# M869D.net
KiCad netlist of a schematic drawn in EAGLE
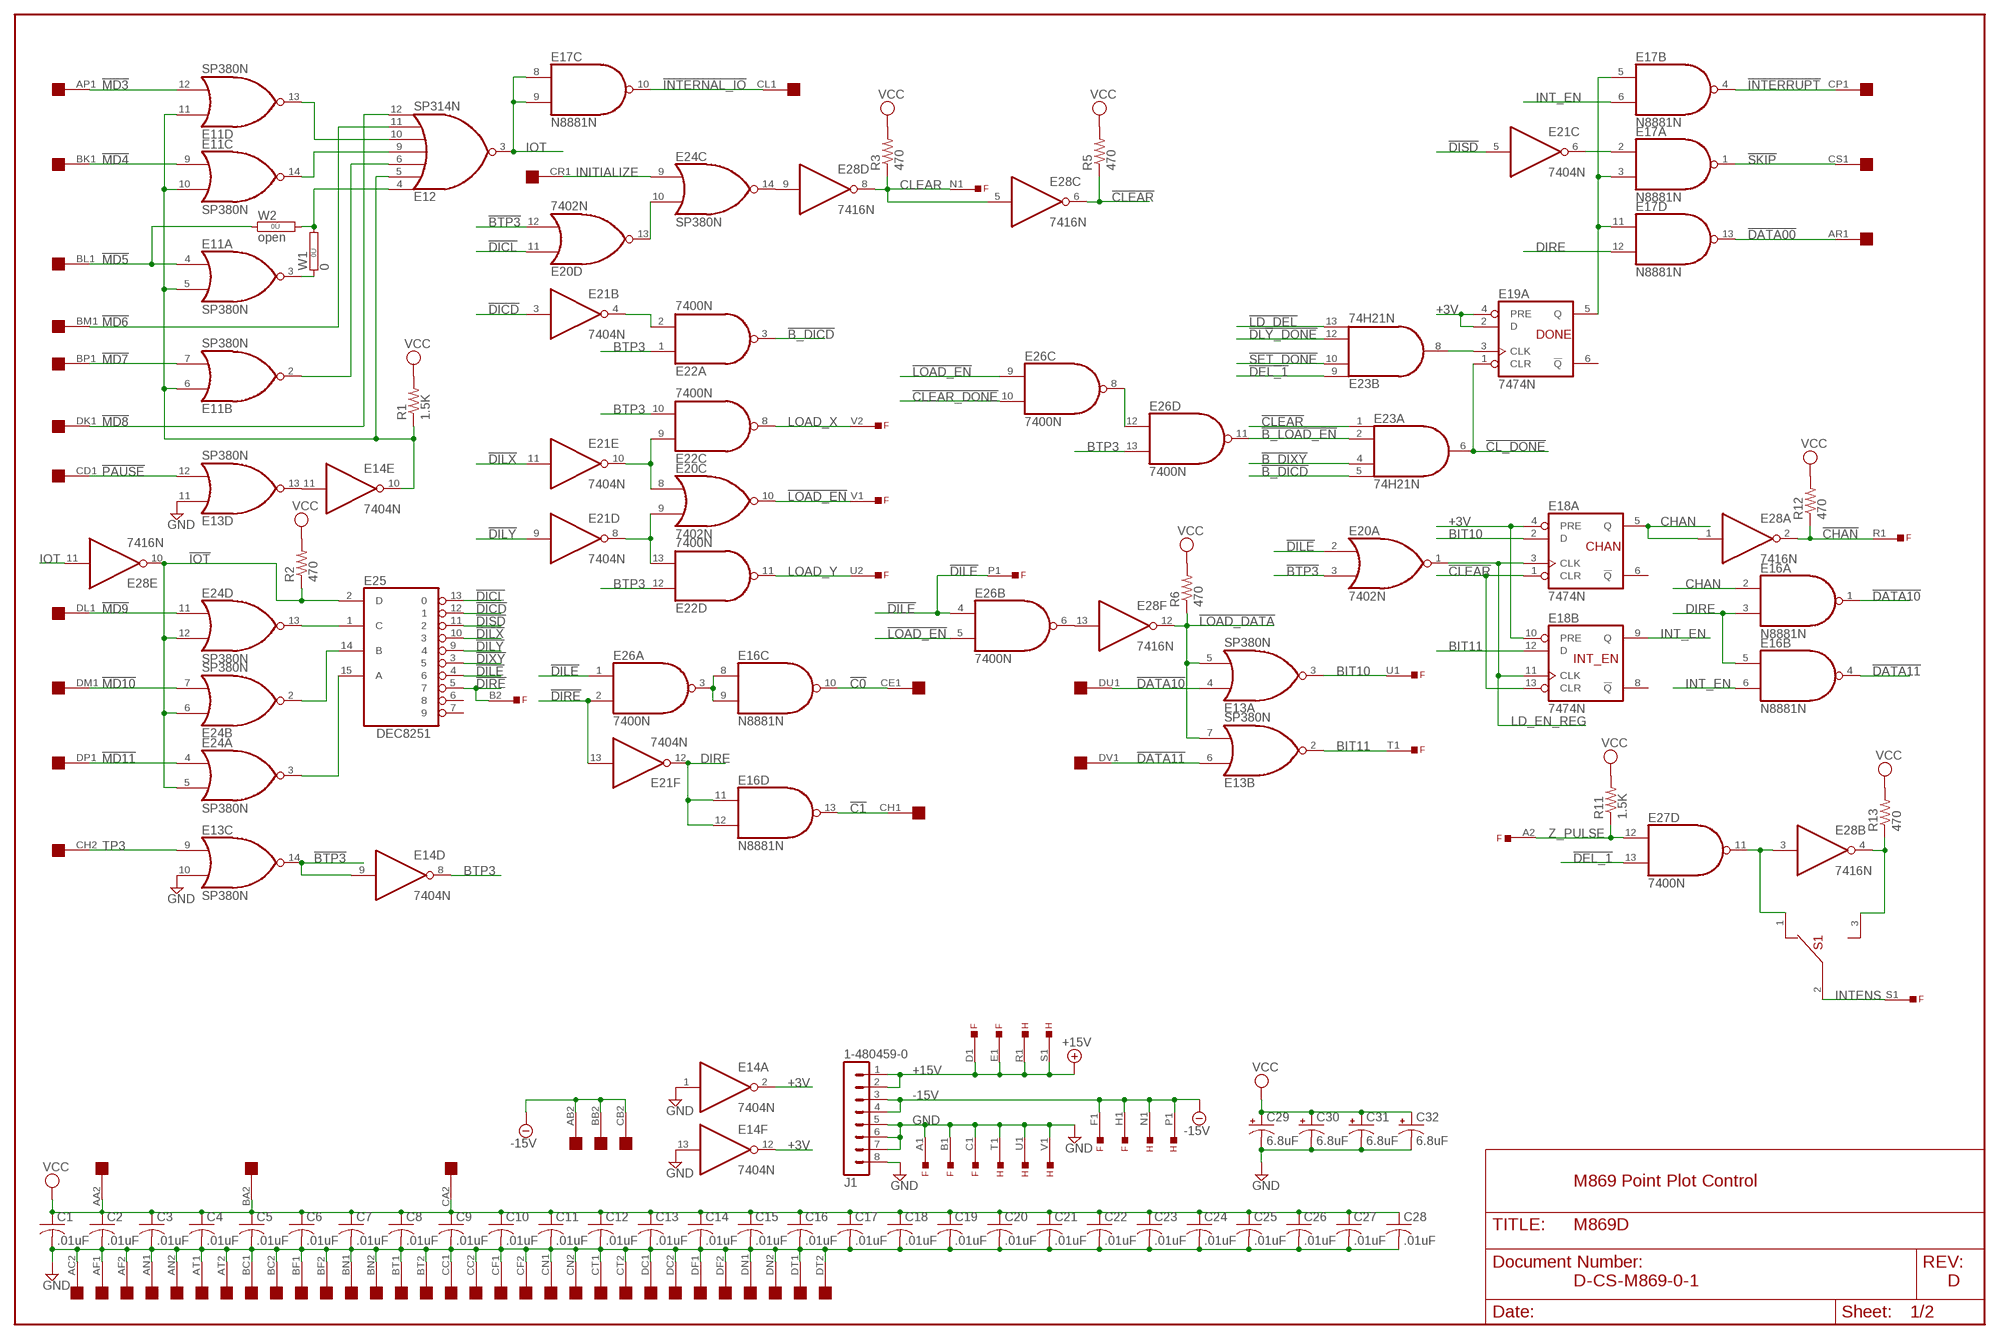
[diagram p0: schematic, sheet 1]
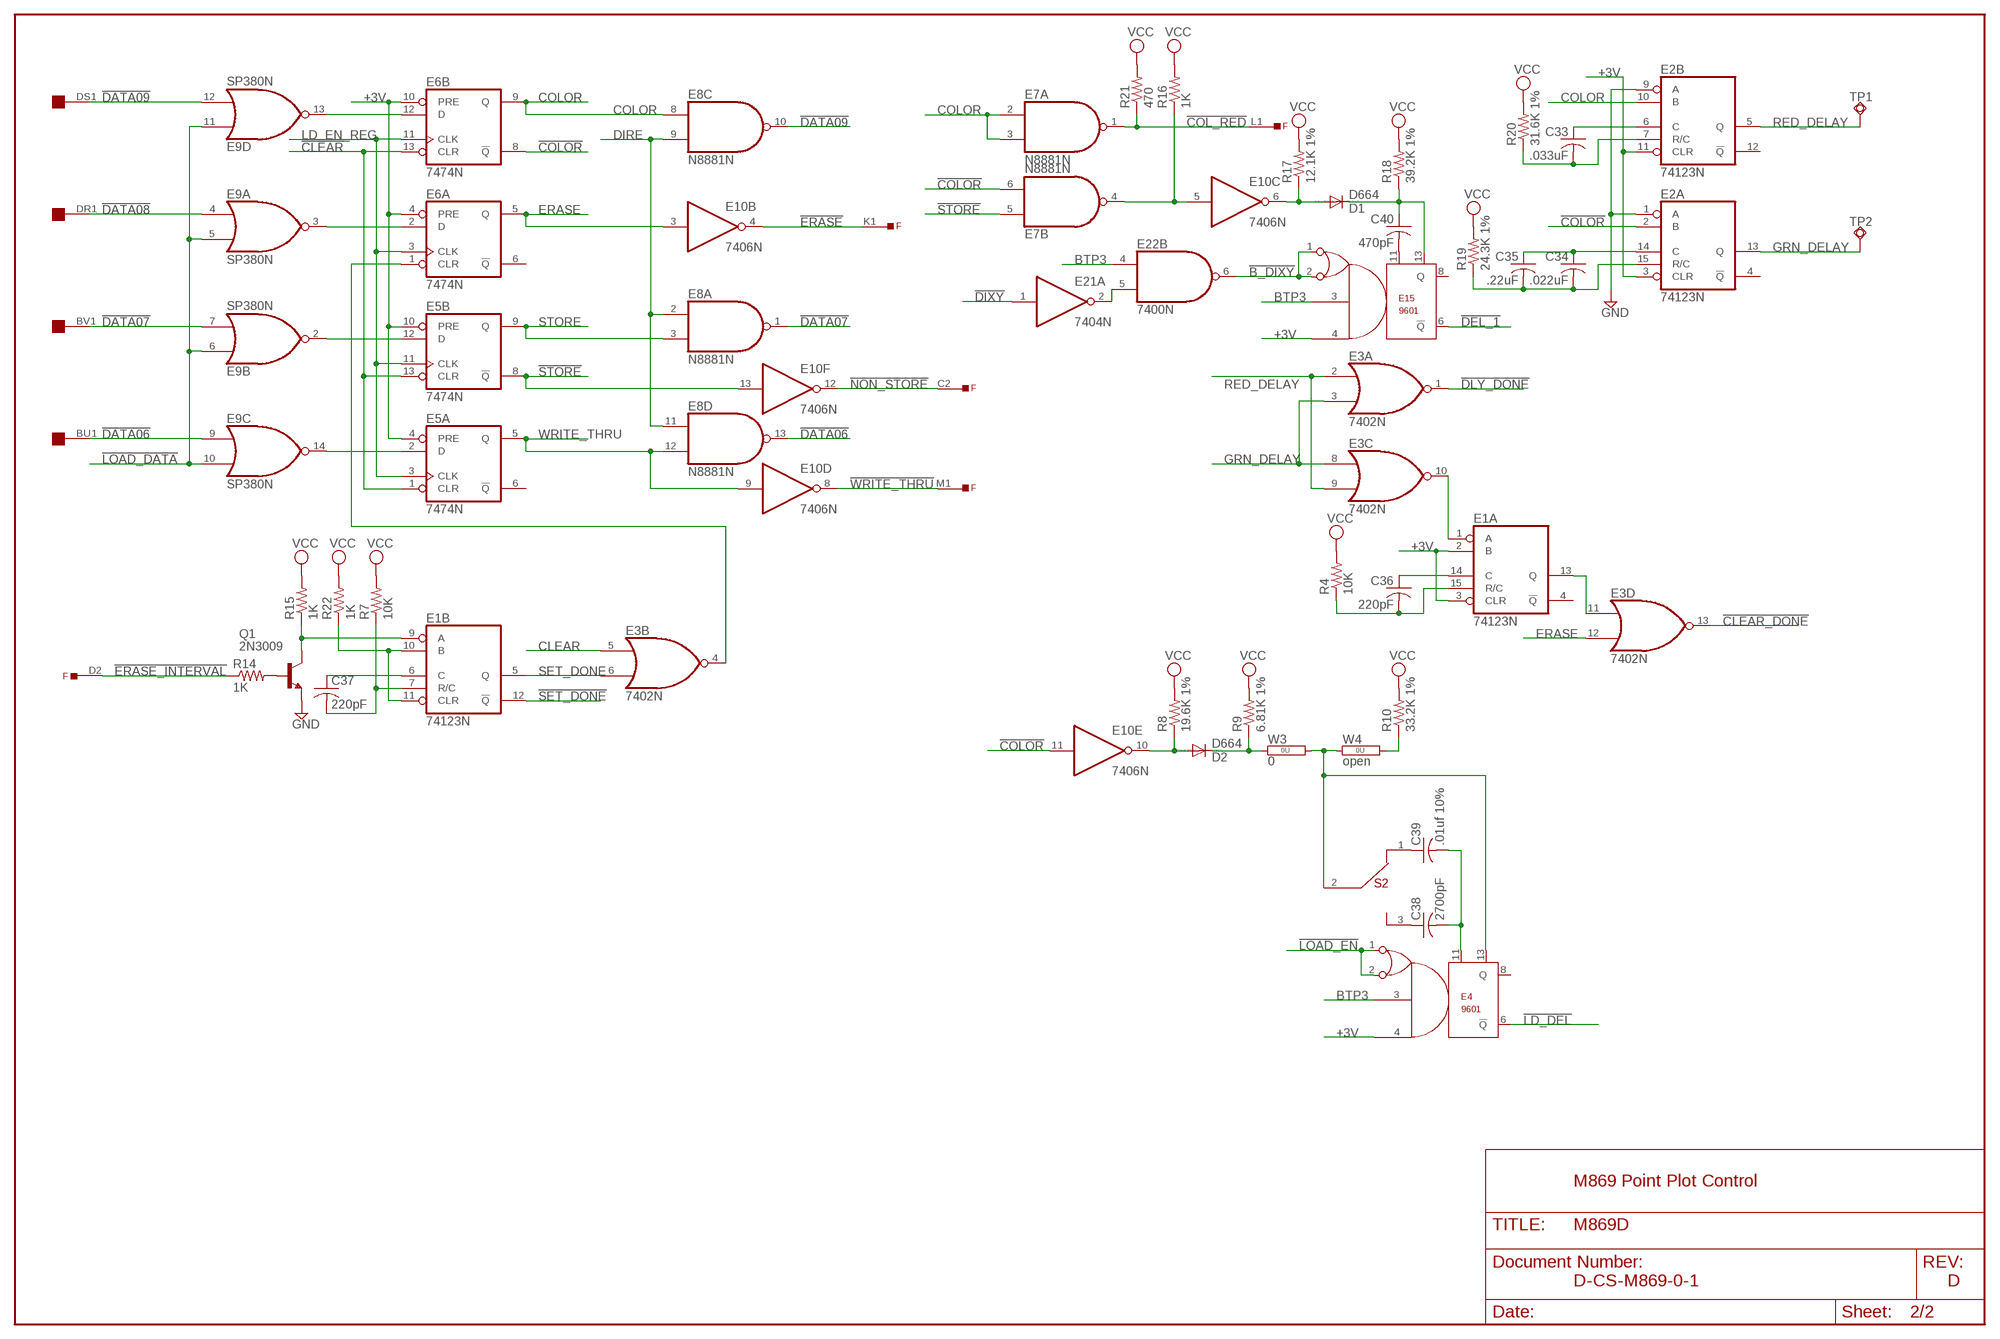
[diagram p1: schematic, sheet 2]

(export (version "E")
  (design (tool "Eeschema 10.0.6"))
  (components
    (comp (ref "C1")
      (value ".01uF")
      (footprint "eagle-import:C063-025X075")
      (libsource (lib "eagle-import") (part "C-US"))
    )
    (comp (ref "C2")
      (value ".01uF")
      (footprint "eagle-import:C063-025X075")
      (libsource (lib "eagle-import") (part "C-US"))
    )
    (comp (ref "C3")
      (value ".01uF")
      (footprint "eagle-import:C063-025X075")
      (libsource (lib "eagle-import") (part "C-US"))
    )
    (comp (ref "C4")
      (value ".01uF")
      (footprint "eagle-import:C063-025X075")
      (libsource (lib "eagle-import") (part "C-US"))
    )
    (comp (ref "C5")
      (value ".01uF")
      (footprint "eagle-import:C063-025X075")
      (libsource (lib "eagle-import") (part "C-US"))
    )
    (comp (ref "C6")
      (value ".01uF")
      (footprint "eagle-import:C063-025X075")
      (libsource (lib "eagle-import") (part "C-US"))
    )
    (comp (ref "C7")
      (value ".01uF")
      (footprint "eagle-import:C063-025X075")
      (libsource (lib "eagle-import") (part "C-US"))
    )
    (comp (ref "C8")
      (value ".01uF")
      (footprint "eagle-import:C063-025X075")
      (libsource (lib "eagle-import") (part "C-US"))
    )
    (comp (ref "C9")
      (value ".01uF")
      (footprint "eagle-import:C063-025X075")
      (libsource (lib "eagle-import") (part "C-US"))
    )
    (comp (ref "C10")
      (value ".01uF")
      (footprint "eagle-import:C063-025X075")
      (libsource (lib "eagle-import") (part "C-US"))
    )
    (comp (ref "C11")
      (value ".01uF")
      (footprint "eagle-import:C063-025X075")
      (libsource (lib "eagle-import") (part "C-US"))
    )
    (comp (ref "C12")
      (value ".01uF")
      (footprint "eagle-import:C063-025X075")
      (libsource (lib "eagle-import") (part "C-US"))
    )
    (comp (ref "C13")
      (value ".01uF")
      (footprint "eagle-import:C063-025X075")
      (libsource (lib "eagle-import") (part "C-US"))
    )
    (comp (ref "C14")
      (value ".01uF")
      (footprint "eagle-import:C063-025X075")
      (libsource (lib "eagle-import") (part "C-US"))
    )
    (comp (ref "C15")
      (value ".01uF")
      (footprint "eagle-import:C063-025X075")
      (libsource (lib "eagle-import") (part "C-US"))
    )
    (comp (ref "C16")
      (value ".01uF")
      (footprint "eagle-import:C063-025X075")
      (libsource (lib "eagle-import") (part "C-US"))
    )
    (comp (ref "C17")
      (value ".01uF")
      (footprint "eagle-import:C063-025X075")
      (libsource (lib "eagle-import") (part "C-US"))
    )
    (comp (ref "C18")
      (value ".01uF")
      (footprint "eagle-import:C063-025X075")
      (libsource (lib "eagle-import") (part "C-US"))
    )
    (comp (ref "C19")
      (value ".01uF")
      (footprint "eagle-import:C063-025X075")
      (libsource (lib "eagle-import") (part "C-US"))
    )
    (comp (ref "C20")
      (value ".01uF")
      (footprint "eagle-import:C063-025X075")
      (libsource (lib "eagle-import") (part "C-US"))
    )
    (comp (ref "C21")
      (value ".01uF")
      (footprint "eagle-import:C063-025X075")
      (libsource (lib "eagle-import") (part "C-US"))
    )
    (comp (ref "C22")
      (value ".01uF")
      (footprint "eagle-import:C063-025X075")
      (libsource (lib "eagle-import") (part "C-US"))
    )
    (comp (ref "C23")
      (value ".01uF")
      (footprint "eagle-import:C063-025X075")
      (libsource (lib "eagle-import") (part "C-US"))
    )
    (comp (ref "C24")
      (value ".01uF")
      (footprint "eagle-import:C063-025X075")
      (libsource (lib "eagle-import") (part "C-US"))
    )
    (comp (ref "C25")
      (value ".01uF")
      (footprint "eagle-import:C063-025X075")
      (libsource (lib "eagle-import") (part "C-US"))
    )
    (comp (ref "C26")
      (value ".01uF")
      (footprint "eagle-import:C063-025X075")
      (libsource (lib "eagle-import") (part "C-US"))
    )
    (comp (ref "C27")
      (value ".01uF")
      (footprint "eagle-import:C063-025X075")
      (libsource (lib "eagle-import") (part "C-US"))
    )
    (comp (ref "C28")
      (value ".01uF")
      (footprint "eagle-import:C063-025X075")
      (libsource (lib "eagle-import") (part "C-US"))
    )
    (comp (ref "C29")
      (value "6.8uF")
      (footprint "eagle-import:E12-8")
      (libsource (lib "eagle-import") (part "CPOL-USE20-8AXIAL"))
    )
    (comp (ref "C30")
      (value "6.8uF")
      (footprint "eagle-import:E12-8")
      (libsource (lib "eagle-import") (part "CPOL-USE20-8AXIAL"))
    )
    (comp (ref "C31")
      (value "6.8uF")
      (footprint "eagle-import:E12-8")
      (libsource (lib "eagle-import") (part "CPOL-USE20-8AXIAL"))
    )
    (comp (ref "C32")
      (value "6.8uF")
      (footprint "eagle-import:E12-8")
      (libsource (lib "eagle-import") (part "CPOL-USE20-8AXIAL"))
    )
    (comp (ref "E11")
      (value "SP380N")
      (footprint "eagle-import:DIL14")
      (libsource (lib "eagle-import") (part "SP380N"))
    )
    (comp (ref "E12")
      (value "SP314N")
      (footprint "eagle-import:DIL14")
      (libsource (lib "eagle-import") (part "SP314N"))
    )
    (comp (ref "E13")
      (value "SP380N")
      (footprint "eagle-import:DIL14")
      (libsource (lib "eagle-import") (part "SP380N"))
    )
    (comp (ref "E14")
      (value "7404N")
      (footprint "eagle-import:DIL14")
      (libsource (lib "eagle-import") (part "7404N"))
    )
    (comp (ref "E16")
      (value "N8881N")
      (footprint "eagle-import:DIL14")
      (libsource (lib "eagle-import") (part "N8881N"))
    )
    (comp (ref "E17")
      (value "N8881N")
      (footprint "eagle-import:DIL14")
      (libsource (lib "eagle-import") (part "N8881N"))
    )
    (comp (ref "E18")
      (value "7474N")
      (footprint "eagle-import:DIL14")
      (libsource (lib "eagle-import") (part "7474NS"))
    )
    (comp (ref "E19")
      (value "7474N")
      (footprint "eagle-import:DIL14")
      (libsource (lib "eagle-import") (part "7474NS"))
    )
    (comp (ref "E20")
      (value "7402N")
      (footprint "eagle-import:DIL14")
      (libsource (lib "eagle-import") (part "7402N"))
    )
    (comp (ref "E21")
      (value "7404N")
      (footprint "eagle-import:DIL14")
      (libsource (lib "eagle-import") (part "7404N"))
    )
    (comp (ref "E22")
      (value "7400N")
      (footprint "eagle-import:DIL14")
      (libsource (lib "eagle-import") (part "7400N"))
    )
    (comp (ref "E23")
      (value "74H21N")
      (footprint "eagle-import:DIL14")
      (libsource (lib "eagle-import") (part "7421NLS"))
    )
    (comp (ref "E24")
      (value "SP380N")
      (footprint "eagle-import:DIL14")
      (libsource (lib "eagle-import") (part "SP380N"))
    )
    (comp (ref "E25")
      (value "DEC8251")
      (footprint "eagle-import:DIL16")
      (libsource (lib "eagle-import") (part "DEC8251"))
    )
    (comp (ref "E26")
      (value "7400N")
      (footprint "eagle-import:DIL14")
      (libsource (lib "eagle-import") (part "7400N"))
    )
    (comp (ref "E27")
      (value "7400N")
      (footprint "eagle-import:DIL14")
      (libsource (lib "eagle-import") (part "7400N"))
    )
    (comp (ref "E28")
      (value "7416N")
      (footprint "eagle-import:DIL14")
      (libsource (lib "eagle-import") (part "7416N"))
    )
    (comp (ref "F")
      (value "EDGE-TOP")
      (footprint "eagle-import:EDGE-CON2")
      (libsource (lib "eagle-import") (part "EDGE-TOP"))
    )
    (comp (ref "H")
      (value "EDGE-TOP")
      (footprint "eagle-import:EDGE-CON2")
      (libsource (lib "eagle-import") (part "EDGE-TOP"))
    )
    (comp (ref "J1")
      (value "1-480459-0")
      (footprint "eagle-import:1-480459-0")
      (libsource (lib "eagle-import") (part "1-480459-0"))
    )
    (comp (ref "OMNIBUS")
      (value "QUAD")
      (footprint "eagle-import:EDGE-CON8")
      (libsource (lib "eagle-import") (part "QUAD"))
    )
    (comp (ref "R1")
      (value "1.5K")
      (footprint "eagle-import:0207_10")
      (libsource (lib "eagle-import") (part "R-US_0207/10"))
    )
    (comp (ref "R2")
      (value "470")
      (footprint "eagle-import:0207_10")
      (libsource (lib "eagle-import") (part "R-US_0207/10"))
    )
    (comp (ref "R3")
      (value "470")
      (footprint "eagle-import:0207_10")
      (libsource (lib "eagle-import") (part "R-US_0207/10"))
    )
    (comp (ref "R5")
      (value "470")
      (footprint "eagle-import:0207_10")
      (libsource (lib "eagle-import") (part "R-US_0207/10"))
    )
    (comp (ref "R6")
      (value "470")
      (footprint "eagle-import:0207_10")
      (libsource (lib "eagle-import") (part "R-US_0207/10"))
    )
    (comp (ref "R11")
      (value "1.5K")
      (footprint "eagle-import:0207_10")
      (libsource (lib "eagle-import") (part "R-US_0207/10"))
    )
    (comp (ref "R12")
      (value "470")
      (footprint "eagle-import:0207_10")
      (libsource (lib "eagle-import") (part "R-US_0207/10"))
    )
    (comp (ref "R13")
      (value "470")
      (footprint "eagle-import:0207_10")
      (libsource (lib "eagle-import") (part "R-US_0207/10"))
    )
    (comp (ref "S1")
      (value "12-09698")
      (footprint "eagle-import:23-021")
      (libsource (lib "eagle-import") (part "12-09698"))
    )
    (comp (ref "W1")
      (value "0")
      (footprint "eagle-import:0R_10")
      (libsource (lib "eagle-import") (part "0R"))
    )
    (comp (ref "W2")
      (value "open")
      (footprint "eagle-import:0R_10")
      (libsource (lib "eagle-import") (part "0R"))
    )
    (comp (ref "C33")
      (value ".033uF")
      (footprint "eagle-import:C325-137X374")
      (libsource (lib "eagle-import") (part "C-US325-137X374"))
    )
    (comp (ref "C34")
      (value ".022uF")
      (footprint "eagle-import:C203-054-229")
      (libsource (lib "eagle-import") (part "C-US8"))
    )
    (comp (ref "C35")
      (value ".22uF")
      (footprint "eagle-import:C203-054-229")
      (libsource (lib "eagle-import") (part "C-US8"))
    )
    (comp (ref "C36")
      (value "220pF")
      (footprint "eagle-import:C063-025X075")
      (libsource (lib "eagle-import") (part "C-US"))
    )
    (comp (ref "C37")
      (value "220pF")
      (footprint "eagle-import:C063-025X075")
      (libsource (lib "eagle-import") (part "C-US"))
    )
    (comp (ref "C38")
      (value "2700pF")
      (footprint "eagle-import:C102-043X133")
      (libsource (lib "eagle-import") (part "C-US102-043X133"))
    )
    (comp (ref "C39")
      (value ".01uf 10%")
      (footprint "eagle-import:C063-025X075")
      (libsource (lib "eagle-import") (part "C-US"))
    )
    (comp (ref "C40")
      (value "470pF")
      (footprint "eagle-import:C063-025X075")
      (libsource (lib "eagle-import") (part "C-US"))
    )
    (comp (ref "D1")
      (value "D664")
      (footprint "eagle-import:DO35-10")
      (libsource (lib "eagle-import") (part "DIODE-DO35-10"))
    )
    (comp (ref "D2")
      (value "D664")
      (footprint "eagle-import:DO35-10")
      (libsource (lib "eagle-import") (part "DIODE-DO35-10"))
    )
    (comp (ref "E1")
      (value "74123N")
      (footprint "eagle-import:DIL16")
      (libsource (lib "eagle-import") (part "74123N"))
    )
    (comp (ref "E2")
      (value "74123N")
      (footprint "eagle-import:DIL16")
      (libsource (lib "eagle-import") (part "74123N"))
    )
    (comp (ref "E3")
      (value "7402N")
      (footprint "eagle-import:DIL14")
      (libsource (lib "eagle-import") (part "7402N"))
    )
    (comp (ref "E4")
      (value "9601")
      (footprint "eagle-import:DIL14")
      (libsource (lib "eagle-import") (part "9601"))
    )
    (comp (ref "E5")
      (value "7474N")
      (footprint "eagle-import:DIL14")
      (libsource (lib "eagle-import") (part "7474NS"))
    )
    (comp (ref "E6")
      (value "7474N")
      (footprint "eagle-import:DIL14")
      (libsource (lib "eagle-import") (part "7474NS"))
    )
    (comp (ref "E7")
      (value "N8881N")
      (footprint "eagle-import:DIL14")
      (libsource (lib "eagle-import") (part "N8881N"))
    )
    (comp (ref "E8")
      (value "N8881N")
      (footprint "eagle-import:DIL14")
      (libsource (lib "eagle-import") (part "N8881N"))
    )
    (comp (ref "E9")
      (value "SP380N")
      (footprint "eagle-import:DIL14")
      (libsource (lib "eagle-import") (part "SP380N"))
    )
    (comp (ref "E10")
      (value "7406N")
      (footprint "eagle-import:DIL14")
      (libsource (lib "eagle-import") (part "7406N"))
    )
    (comp (ref "E15")
      (value "9601")
      (footprint "eagle-import:DIL14")
      (libsource (lib "eagle-import") (part "9601"))
    )
    (comp (ref "Q1")
      (value "2N3009")
      (footprint "eagle-import:TO18-")
      (libsource (lib "eagle-import") (part "-NPN-TO18-"))
    )
    (comp (ref "R4")
      (value "10K")
      (footprint "eagle-import:0207_10")
      (libsource (lib "eagle-import") (part "R-US_0207/10"))
    )
    (comp (ref "R7")
      (value "10K")
      (footprint "eagle-import:0207_10")
      (libsource (lib "eagle-import") (part "R-US_0207/10"))
    )
    (comp (ref "R8")
      (value "19.6K 1%")
      (footprint "eagle-import:0207_15")
      (libsource (lib "eagle-import") (part "R-US_0207/15"))
    )
    (comp (ref "R9")
      (value "6.81K 1%")
      (footprint "eagle-import:0207_15")
      (libsource (lib "eagle-import") (part "R-US_0207/15"))
    )
    (comp (ref "R10")
      (value "33.2K 1%")
      (footprint "eagle-import:0207_15")
      (libsource (lib "eagle-import") (part "R-US_0207/15"))
    )
    (comp (ref "R14")
      (value "1K")
      (footprint "eagle-import:0207_10")
      (libsource (lib "eagle-import") (part "R-US_0207/10"))
    )
    (comp (ref "R15")
      (value "1K")
      (footprint "eagle-import:0207_10")
      (libsource (lib "eagle-import") (part "R-US_0207/10"))
    )
    (comp (ref "R16")
      (value "1K")
      (footprint "eagle-import:0207_10")
      (libsource (lib "eagle-import") (part "R-US_0207/10"))
    )
    (comp (ref "R17")
      (value "12.1K 1%")
      (footprint "eagle-import:0207_15")
      (libsource (lib "eagle-import") (part "R-US_0207/15"))
    )
    (comp (ref "R18")
      (value "39.2K 1%")
      (footprint "eagle-import:0207_15")
      (libsource (lib "eagle-import") (part "R-US_0207/15"))
    )
    (comp (ref "R19")
      (value "24.3K 1%")
      (footprint "eagle-import:0207_15")
      (libsource (lib "eagle-import") (part "R-US_0207/15"))
    )
    (comp (ref "R20")
      (value "31.6K 1%")
      (footprint "eagle-import:0207_15")
      (libsource (lib "eagle-import") (part "R-US_0207/15"))
    )
    (comp (ref "R21")
      (value "470")
      (footprint "eagle-import:0207_10")
      (libsource (lib "eagle-import") (part "R-US_0207/10"))
    )
    (comp (ref "R22")
      (value "1K")
      (footprint "eagle-import:0207_10")
      (libsource (lib "eagle-import") (part "R-US_0207/10"))
    )
    (comp (ref "S2")
      (value "12-09698")
      (footprint "eagle-import:23-021")
      (libsource (lib "eagle-import") (part "12-09698"))
    )
    (comp (ref "TP1")
      (value "TPSQPAD1-17")
      (footprint "eagle-import:P1-17")
      (libsource (lib "eagle-import") (part "TPSQPAD1-17"))
    )
    (comp (ref "TP2")
      (value "TPSQPAD1-17")
      (footprint "eagle-import:P1-17")
      (libsource (lib "eagle-import") (part "TPSQPAD1-17"))
    )
    (comp (ref "W3")
      (value "0")
      (footprint "eagle-import:0R_10")
      (libsource (lib "eagle-import") (part "0R"))
    )
    (comp (ref "W4")
      (value "open")
      (footprint "eagle-import:0R_10")
      (libsource (lib "eagle-import") (part "0R"))
    )
  )
  (nets
    (net (code "1") (name "+3V") (class "Default")
      (node (ref "E1") (pin "2") (pinfunction "B_2") (pintype "input"))
      (node (ref "E1") (pin "3") (pinfunction "CLR_3") (pintype "input"))
      (node (ref "E14") (pin "12") (pinfunction "O_12") (pintype "output"))
      (node (ref "E14") (pin "2") (pinfunction "O_2") (pintype "output"))
      (node (ref "E15") (pin "4") (pinfunction "P$4_4") (pintype "input"))
      (node (ref "E18") (pin "10") (pinfunction "PRE_10") (pintype "input"))
      (node (ref "E18") (pin "4") (pinfunction "PRE_4") (pintype "input"))
      (node (ref "E19") (pin "2") (pinfunction "D_2") (pintype "input"))
      (node (ref "E19") (pin "4") (pinfunction "PRE_4") (pintype "input"))
      (node (ref "E2") (pin "11") (pinfunction "CLR_11") (pintype "input"))
      (node (ref "E2") (pin "3") (pinfunction "CLR_3") (pintype "input"))
      (node (ref "E4") (pin "4") (pinfunction "P$4_4") (pintype "input"))
      (node (ref "E5") (pin "10") (pinfunction "PRE_10") (pintype "input"))
      (node (ref "E5") (pin "4") (pinfunction "PRE_4") (pintype "input"))
      (node (ref "E6") (pin "10") (pinfunction "PRE_10") (pintype "input"))
      (node (ref "E6") (pin "4") (pinfunction "PRE_4") (pintype "input"))
    )
    (net (code "2") (name "+15V") (class "Default")
      (node (ref "F") (pin "D1") (pinfunction "P_D1") (pintype "passive"))
      (node (ref "F") (pin "E1") (pinfunction "P_E1") (pintype "passive"))
      (node (ref "H") (pin "R1") (pinfunction "P_R1") (pintype "passive"))
      (node (ref "H") (pin "S1") (pinfunction "P_S1") (pintype "passive"))
      (node (ref "J1") (pin "1") (pinfunction "1_1") (pintype "passive"))
      (node (ref "J1") (pin "2") (pinfunction "2_2") (pintype "passive"))
    )
    (net (code "3") (name "-15V") (class "Default")
      (node (ref "F") (pin "F1") (pinfunction "P_F1") (pintype "passive"))
      (node (ref "F") (pin "H1") (pinfunction "P_H1") (pintype "passive"))
      (node (ref "H") (pin "N1") (pinfunction "P_N1") (pintype "passive"))
      (node (ref "H") (pin "P1") (pinfunction "P_P1") (pintype "passive"))
      (node (ref "J1") (pin "3") (pinfunction "3_3") (pintype "passive"))
      (node (ref "J1") (pin "4") (pinfunction "4_4") (pintype "passive"))
      (node (ref "OMNIBUS") (pin "AB2") (pinfunction "1_AB2") (pintype "bidirectional"))
      (node (ref "OMNIBUS") (pin "BB2") (pinfunction "1_BB2") (pintype "bidirectional"))
      (node (ref "OMNIBUS") (pin "CB2") (pinfunction "1_CB2") (pintype "bidirectional"))
    )
    (net (code "4") (name "BIT10") (class "Default")
      (node (ref "E13") (pin "3") (pinfunction "O_3") (pintype "output"))
      (node (ref "E18") (pin "2") (pinfunction "D_2") (pintype "input"))
      (node (ref "F") (pin "U1") (pinfunction "P_U1") (pintype "passive"))
    )
    (net (code "5") (name "BIT11") (class "Default")
      (node (ref "E13") (pin "2") (pinfunction "O_2") (pintype "output"))
      (node (ref "E18") (pin "12") (pinfunction "D_12") (pintype "input"))
      (node (ref "F") (pin "T1") (pinfunction "P_T1") (pintype "passive"))
    )
    (net (code "6") (name "BTP3") (class "Default")
      (node (ref "E14") (pin "8") (pinfunction "O_8") (pintype "output"))
      (node (ref "E15") (pin "3") (pinfunction "P$3_3") (pintype "input"))
      (node (ref "E22") (pin "1") (pinfunction "I0_1") (pintype "input"))
      (node (ref "E22") (pin "10") (pinfunction "I1_10") (pintype "input"))
      (node (ref "E22") (pin "12") (pinfunction "I0_12") (pintype "input"))
      (node (ref "E22") (pin "4") (pinfunction "I0_4") (pintype "input"))
      (node (ref "E26") (pin "13") (pinfunction "I1_13") (pintype "input"))
      (node (ref "E4") (pin "3") (pinfunction "P$3_3") (pintype "input"))
    )
    (net (code "7") (name "CHAN") (class "Default")
      (node (ref "E16") (pin "2") (pinfunction "I0_2") (pintype "input"))
      (node (ref "E18") (pin "5") (pinfunction "Q_5") (pintype "output"))
      (node (ref "E28") (pin "1") (pinfunction "I_1") (pintype "input"))
    )
    (net (code "8") (name "CLEAR") (class "Default")
      (node (ref "E28") (pin "5") (pinfunction "I_5") (pintype "input"))
      (node (ref "E28") (pin "8") (pinfunction "O_8") (pintype "open_collector"))
      (node (ref "E3") (pin "5") (pinfunction "I0_5") (pintype "input"))
      (node (ref "F") (pin "N1") (pinfunction "P_N1") (pintype "passive"))
      (node (ref "R3") (pin "1") (pinfunction "1_1") (pintype "passive"))
    )
    (net (code "9") (name "COLOR") (class "Default")
      (node (ref "E2") (pin "10") (pinfunction "B_10") (pintype "input"))
      (node (ref "E6") (pin "9") (pinfunction "Q_9") (pintype "output"))
      (node (ref "E7") (pin "2") (pinfunction "I0_2") (pintype "input"))
      (node (ref "E7") (pin "3") (pinfunction "I1_3") (pintype "input"))
      (node (ref "E8") (pin "8") (pinfunction "I0_8") (pintype "input"))
    )
    (net (code "10") (name "DIRE") (class "Default")
      (node (ref "E16") (pin "11") (pinfunction "I0_11") (pintype "input"))
      (node (ref "E16") (pin "12") (pinfunction "I1_12") (pintype "input"))
      (node (ref "E16") (pin "3") (pinfunction "I1_3") (pintype "input"))
      (node (ref "E16") (pin "5") (pinfunction "I0_5") (pintype "input"))
      (node (ref "E17") (pin "12") (pinfunction "I1_12") (pintype "input"))
      (node (ref "E21") (pin "12") (pinfunction "O_12") (pintype "output"))
      (node (ref "E8") (pin "11") (pinfunction "I0_11") (pintype "input"))
      (node (ref "E8") (pin "2") (pinfunction "I0_2") (pintype "input"))
      (node (ref "E8") (pin "9") (pinfunction "I1_9") (pintype "input"))
    )
    (net (code "11") (name "ERASE") (class "Default")
      (node (ref "E10") (pin "3") (pinfunction "I_3") (pintype "input"))
      (node (ref "E3") (pin "12") (pinfunction "I1_12") (pintype "input"))
      (node (ref "E6") (pin "5") (pinfunction "Q_5") (pintype "output"))
    )
    (net (code "12") (name "GND") (class "Default")
      (node (ref "C1") (pin "2") (pinfunction "2_2") (pintype "passive"))
      (node (ref "C10") (pin "2") (pinfunction "2_2") (pintype "passive"))
      (node (ref "C11") (pin "2") (pinfunction "2_2") (pintype "passive"))
      (node (ref "C12") (pin "2") (pinfunction "2_2") (pintype "passive"))
      (node (ref "C13") (pin "2") (pinfunction "2_2") (pintype "passive"))
      (node (ref "C14") (pin "2") (pinfunction "2_2") (pintype "passive"))
      (node (ref "C15") (pin "2") (pinfunction "2_2") (pintype "passive"))
      (node (ref "C16") (pin "2") (pinfunction "2_2") (pintype "passive"))
      (node (ref "C17") (pin "2") (pinfunction "2_2") (pintype "passive"))
      (node (ref "C18") (pin "2") (pinfunction "2_2") (pintype "passive"))
      (node (ref "C19") (pin "2") (pinfunction "2_2") (pintype "passive"))
      (node (ref "C2") (pin "2") (pinfunction "2_2") (pintype "passive"))
      (node (ref "C20") (pin "2") (pinfunction "2_2") (pintype "passive"))
      (node (ref "C21") (pin "2") (pinfunction "2_2") (pintype "passive"))
      (node (ref "C22") (pin "2") (pinfunction "2_2") (pintype "passive"))
      (node (ref "C23") (pin "2") (pinfunction "2_2") (pintype "passive"))
      (node (ref "C24") (pin "2") (pinfunction "2_2") (pintype "passive"))
      (node (ref "C25") (pin "2") (pinfunction "2_2") (pintype "passive"))
      (node (ref "C26") (pin "2") (pinfunction "2_2") (pintype "passive"))
      (node (ref "C27") (pin "2") (pinfunction "2_2") (pintype "passive"))
      (node (ref "C28") (pin "2") (pinfunction "2_2") (pintype "passive"))
      (node (ref "C29") (pin "-") (pinfunction "-_-") (pintype "passive"))
      (node (ref "C3") (pin "2") (pinfunction "2_2") (pintype "passive"))
      (node (ref "C30") (pin "-") (pinfunction "-_-") (pintype "passive"))
      (node (ref "C31") (pin "-") (pinfunction "-_-") (pintype "passive"))
      (node (ref "C32") (pin "-") (pinfunction "-_-") (pintype "passive"))
      (node (ref "C4") (pin "2") (pinfunction "2_2") (pintype "passive"))
      (node (ref "C5") (pin "2") (pinfunction "2_2") (pintype "passive"))
      (node (ref "C6") (pin "2") (pinfunction "2_2") (pintype "passive"))
      (node (ref "C7") (pin "2") (pinfunction "2_2") (pintype "passive"))
      (node (ref "C8") (pin "2") (pinfunction "2_2") (pintype "passive"))
      (node (ref "C9") (pin "2") (pinfunction "2_2") (pintype "passive"))
      (node (ref "E13") (pin "10") (pinfunction "I1_10") (pintype "input"))
      (node (ref "E13") (pin "11") (pinfunction "I0_11") (pintype "input"))
      (node (ref "E14") (pin "1") (pinfunction "I_1") (pintype "input"))
      (node (ref "E14") (pin "13") (pinfunction "I_13") (pintype "input"))
      (node (ref "E2") (pin "1") (pinfunction "A_1") (pintype "input"))
      (node (ref "E2") (pin "9") (pinfunction "A_9") (pintype "input"))
      (node (ref "F") (pin "A1") (pinfunction "P_A1") (pintype "passive"))
      (node (ref "F") (pin "B1") (pinfunction "P_B1") (pintype "passive"))
      (node (ref "F") (pin "C1") (pinfunction "P_C1") (pintype "passive"))
      (node (ref "H") (pin "T1") (pinfunction "P_T1") (pintype "passive"))
      (node (ref "H") (pin "U1") (pinfunction "P_U1") (pintype "passive"))
      (node (ref "H") (pin "V1") (pinfunction "P_V1") (pintype "passive"))
      (node (ref "J1") (pin "5") (pinfunction "5_5") (pintype "passive"))
      (node (ref "J1") (pin "6") (pinfunction "6_6") (pintype "passive"))
      (node (ref "J1") (pin "7") (pinfunction "7_7") (pintype "passive"))
      (node (ref "J1") (pin "8") (pinfunction "8_8") (pintype "passive"))
      (node (ref "OMNIBUS") (pin "AC2") (pinfunction "1_AC2") (pintype "bidirectional"))
      (node (ref "OMNIBUS") (pin "AF1") (pinfunction "1_AF1") (pintype "bidirectional"))
      (node (ref "OMNIBUS") (pin "AF2") (pinfunction "1_AF2") (pintype "bidirectional"))
      (node (ref "OMNIBUS") (pin "AN1") (pinfunction "1_AN1") (pintype "bidirectional"))
      (node (ref "OMNIBUS") (pin "AN2") (pinfunction "1_AN2") (pintype "bidirectional"))
      (node (ref "OMNIBUS") (pin "AT1") (pinfunction "1_AT1") (pintype "bidirectional"))
      (node (ref "OMNIBUS") (pin "AT2") (pinfunction "1_AT2") (pintype "bidirectional"))
      (node (ref "OMNIBUS") (pin "BC1") (pinfunction "1_BC1") (pintype "bidirectional"))
      (node (ref "OMNIBUS") (pin "BC2") (pinfunction "1_BC2") (pintype "bidirectional"))
      (node (ref "OMNIBUS") (pin "BF1") (pinfunction "1_BF1") (pintype "bidirectional"))
      (node (ref "OMNIBUS") (pin "BF2") (pinfunction "1_BF2") (pintype "bidirectional"))
      (node (ref "OMNIBUS") (pin "BN1") (pinfunction "1_BN1") (pintype "bidirectional"))
      (node (ref "OMNIBUS") (pin "BN2") (pinfunction "1_BN2") (pintype "bidirectional"))
      (node (ref "OMNIBUS") (pin "BT1") (pinfunction "1_BT1") (pintype "bidirectional"))
      (node (ref "OMNIBUS") (pin "BT2") (pinfunction "1_BT2") (pintype "bidirectional"))
      (node (ref "OMNIBUS") (pin "CC1") (pinfunction "1_CC1") (pintype "bidirectional"))
      (node (ref "OMNIBUS") (pin "CC2") (pinfunction "1_CC2") (pintype "bidirectional"))
      (node (ref "OMNIBUS") (pin "CF1") (pinfunction "1_CF1") (pintype "bidirectional"))
      (node (ref "OMNIBUS") (pin "CF2") (pinfunction "1_CF2") (pintype "bidirectional"))
      (node (ref "OMNIBUS") (pin "CN1") (pinfunction "1_CN1") (pintype "bidirectional"))
      (node (ref "OMNIBUS") (pin "CN2") (pinfunction "1_CN2") (pintype "bidirectional"))
      (node (ref "OMNIBUS") (pin "CT1") (pinfunction "1_CT1") (pintype "bidirectional"))
      (node (ref "OMNIBUS") (pin "CT2") (pinfunction "1_CT2") (pintype "bidirectional"))
      (node (ref "OMNIBUS") (pin "DC1") (pinfunction "1_DC1") (pintype "bidirectional"))
      (node (ref "OMNIBUS") (pin "DC2") (pinfunction "1_DC2") (pintype "bidirectional"))
      (node (ref "OMNIBUS") (pin "DF1") (pinfunction "1_DF1") (pintype "bidirectional"))
      (node (ref "OMNIBUS") (pin "DF2") (pinfunction "1_DF2") (pintype "bidirectional"))
      (node (ref "OMNIBUS") (pin "DN1") (pinfunction "1_DN1") (pintype "bidirectional"))
      (node (ref "OMNIBUS") (pin "DN2") (pinfunction "1_DN2") (pintype "bidirectional"))
      (node (ref "OMNIBUS") (pin "DT1") (pinfunction "1_DT1") (pintype "bidirectional"))
      (node (ref "OMNIBUS") (pin "DT2") (pinfunction "1_DT2") (pintype "bidirectional"))
      (node (ref "Q1") (pin "1") (pinfunction "E_1") (pintype "passive"))
    )
    (net (code "13") (name "GRN_DELAY") (class "Default")
      (node (ref "E2") (pin "13") (pinfunction "Q_13") (pintype "output"))
      (node (ref "E3") (pin "3") (pinfunction "I1_3") (pintype "input"))
      (node (ref "E3") (pin "8") (pinfunction "I0_8") (pintype "input"))
      (node (ref "TP2") (pin "TP") (pinfunction "TP_TP") (pintype "input"))
    )
    (net (code "14") (name "INITIALIZE") (class "Default")
      (node (ref "E24") (pin "9") (pinfunction "I0_9") (pintype "input"))
      (node (ref "OMNIBUS") (pin "CR1") (pinfunction "1_CR1") (pintype "bidirectional"))
    )
    (net (code "15") (name "INTENS") (class "Default")
      (node (ref "F") (pin "S1") (pinfunction "P_S1") (pintype "passive"))
      (node (ref "S1") (pin "2") (pinfunction "A2_2") (pintype "bidirectional"))
    )
    (net (code "16") (name "INT_EN") (class "Default")
      (node (ref "E16") (pin "6") (pinfunction "I1_6") (pintype "input"))
      (node (ref "E17") (pin "6") (pinfunction "I1_6") (pintype "input"))
      (node (ref "E18") (pin "9") (pinfunction "Q_9") (pintype "output"))
    )
    (net (code "17") (name "IOT") (class "Default")
      (node (ref "E12") (pin "3") (pinfunction "O_3") (pintype "output"))
      (node (ref "E17") (pin "8") (pinfunction "I0_8") (pintype "input"))
      (node (ref "E17") (pin "9") (pinfunction "I1_9") (pintype "input"))
      (node (ref "E28") (pin "11") (pinfunction "I_11") (pintype "input"))
    )
    (net (code "18") (name "LD_EN_REG") (class "Default")
      (node (ref "E18") (pin "11") (pinfunction "CLK_11") (pintype "input"))
      (node (ref "E18") (pin "3") (pinfunction "CLK_3") (pintype "input"))
      (node (ref "E20") (pin "1") (pinfunction "O_1") (pintype "output"))
      (node (ref "E5") (pin "11") (pinfunction "CLK_11") (pintype "input"))
      (node (ref "E5") (pin "3") (pinfunction "CLK_3") (pintype "input"))
      (node (ref "E6") (pin "11") (pinfunction "CLK_11") (pintype "input"))
      (node (ref "E6") (pin "3") (pinfunction "CLK_3") (pintype "input"))
    )
    (net (code "19") (name "LOAD_X") (class "Default")
      (node (ref "E22") (pin "8") (pinfunction "O_8") (pintype "output"))
      (node (ref "F") (pin "V2") (pinfunction "P_V2") (pintype "passive"))
    )
    (net (code "20") (name "LOAD_Y") (class "Default")
      (node (ref "E22") (pin "11") (pinfunction "O_11") (pintype "output"))
      (node (ref "F") (pin "U2") (pinfunction "P_U2") (pintype "passive"))
    )
    (net (code "21") (name "Net-(D2-PadC)") (class "Default")
      (node (ref "D2") (pin "C") (pinfunction "C_C") (pintype "passive"))
      (node (ref "R9") (pin "1") (pinfunction "1_1") (pintype "passive"))
      (node (ref "W3") (pin "1") (pinfunction "1_1") (pintype "passive"))
    )
    (net (code "22") (name "Net-(E1A-A)") (class "Default")
      (node (ref "E1") (pin "1") (pinfunction "A_1") (pintype "input"))
      (node (ref "E3") (pin "10") (pinfunction "O_10") (pintype "output"))
    )
    (net (code "23") (name "Net-(E1A-C)") (class "Default")
      (node (ref "C36") (pin "1") (pinfunction "1_1") (pintype "passive"))
      (node (ref "E1") (pin "14") (pinfunction "C_14") (pintype "input"))
    )
    (net (code "24") (name "Net-(E1A-Q)") (class "Default")
      (node (ref "E1") (pin "13") (pinfunction "Q_13") (pintype "output"))
      (node (ref "E3") (pin "11") (pinfunction "I0_11") (pintype "input"))
    )
    (net (code "25") (name "Net-(E1A-R{slash}C)") (class "Default")
      (node (ref "C36") (pin "2") (pinfunction "2_2") (pintype "passive"))
      (node (ref "E1") (pin "15") (pinfunction "R/C_15") (pintype "input"))
      (node (ref "R4") (pin "1") (pinfunction "1_1") (pintype "passive"))
    )
    (net (code "26") (name "Net-(E1B-A)") (class "Default")
      (node (ref "E1") (pin "9") (pinfunction "A_9") (pintype "input"))
      (node (ref "Q1") (pin "3") (pinfunction "C_3") (pintype "passive"))
      (node (ref "R15") (pin "1") (pinfunction "1_1") (pintype "passive"))
    )
    (net (code "27") (name "Net-(E1B-B)") (class "Default")
      (node (ref "E1") (pin "10") (pinfunction "B_10") (pintype "input"))
      (node (ref "E1") (pin "11") (pinfunction "CLR_11") (pintype "input"))
      (node (ref "R22") (pin "1") (pinfunction "1_1") (pintype "passive"))
    )
    (net (code "28") (name "Net-(E1B-C)") (class "Default")
      (node (ref "C37") (pin "1") (pinfunction "1_1") (pintype "passive"))
      (node (ref "E1") (pin "6") (pinfunction "C_6") (pintype "input"))
    )
    (net (code "29") (name "Net-(E1B-R{slash}C)") (class "Default")
      (node (ref "C37") (pin "2") (pinfunction "2_2") (pintype "passive"))
      (node (ref "E1") (pin "7") (pinfunction "R/C_7") (pintype "input"))
      (node (ref "R7") (pin "1") (pinfunction "1_1") (pintype "passive"))
    )
    (net (code "30") (name "Net-(E2A-C)") (class "Default")
      (node (ref "C34") (pin "1") (pinfunction "1_1") (pintype "passive"))
      (node (ref "C35") (pin "1") (pinfunction "1_1") (pintype "passive"))
      (node (ref "E2") (pin "14") (pinfunction "C_14") (pintype "input"))
    )
    (net (code "31") (name "Net-(E2A-R{slash}C)") (class "Default")
      (node (ref "C34") (pin "2") (pinfunction "2_2") (pintype "passive"))
      (node (ref "C35") (pin "2") (pinfunction "2_2") (pintype "passive"))
      (node (ref "E2") (pin "15") (pinfunction "R/C_15") (pintype "input"))
      (node (ref "R19") (pin "1") (pinfunction "1_1") (pintype "passive"))
    )
    (net (code "32") (name "Net-(E2B-C)") (class "Default")
      (node (ref "C33") (pin "1") (pinfunction "1_1") (pintype "passive"))
      (node (ref "E2") (pin "6") (pinfunction "C_6") (pintype "input"))
    )
    (net (code "33") (name "Net-(E2B-R{slash}C)") (class "Default")
      (node (ref "C33") (pin "2") (pinfunction "2_2") (pintype "passive"))
      (node (ref "E2") (pin "7") (pinfunction "R/C_7") (pintype "input"))
      (node (ref "R20") (pin "1") (pinfunction "1_1") (pintype "passive"))
    )
    (net (code "34") (name "Net-(E3B-O)") (class "Default")
      (node (ref "E3") (pin "4") (pinfunction "O_4") (pintype "output"))
      (node (ref "E6") (pin "1") (pinfunction "CLR_1") (pintype "input"))
    )
    (net (code "35") (name "Net-(E4A-P$5)") (class "Default")
      (node (ref "C38") (pin "2") (pinfunction "2_2") (pintype "passive"))
      (node (ref "C39") (pin "2") (pinfunction "2_2") (pintype "passive"))
      (node (ref "E4") (pin "11") (pinfunction "P$5_11") (pintype "bidirectional"))
    )
    (net (code "36") (name "Net-(E4A-P$6)") (class "Default")
      (node (ref "E4") (pin "13") (pinfunction "P$6_13") (pintype "bidirectional"))
      (node (ref "S2") (pin "2") (pinfunction "A2_2") (pintype "bidirectional"))
      (node (ref "W3") (pin "2") (pinfunction "2_2") (pintype "passive"))
      (node (ref "W4") (pin "1") (pinfunction "1_1") (pintype "passive"))
    )
    (net (code "37") (name "Net-(E5A-D)") (class "Default")
      (node (ref "E5") (pin "2") (pinfunction "D_2") (pintype "input"))
      (node (ref "E9") (pin "14") (pinfunction "O_14") (pintype "output"))
    )
    (net (code "38") (name "Net-(E5B-D)") (class "Default")
      (node (ref "E5") (pin "12") (pinfunction "D_12") (pintype "input"))
      (node (ref "E9") (pin "2") (pinfunction "O_2") (pintype "output"))
    )
    (net (code "39") (name "Net-(E6A-D)") (class "Default")
      (node (ref "E6") (pin "2") (pinfunction "D_2") (pintype "input"))
      (node (ref "E9") (pin "3") (pinfunction "O_3") (pintype "output"))
    )
    (net (code "40") (name "Net-(E6B-D)") (class "Default")
      (node (ref "E6") (pin "12") (pinfunction "D_12") (pintype "input"))
      (node (ref "E9") (pin "13") (pinfunction "O_13") (pintype "output"))
    )
    (net (code "41") (name "Net-(E10C-I)") (class "Default")
      (node (ref "E10") (pin "5") (pinfunction "I_5") (pintype "input"))
      (node (ref "E7") (pin "4") (pinfunction "O_4") (pintype "open_collector"))
      (node (ref "R16") (pin "1") (pinfunction "1_1") (pintype "passive"))
    )
    (net (code "42") (name "Net-(E10C-O)") (class "Default")
      (node (ref "D1") (pin "A") (pinfunction "A_A") (pintype "passive"))
      (node (ref "E10") (pin "6") (pinfunction "O_6") (pintype "open_collector"))
      (node (ref "R17") (pin "1") (pinfunction "1_1") (pintype "passive"))
    )
    (net (code "43") (name "Net-(E10E-O)") (class "Default")
      (node (ref "D2") (pin "A") (pinfunction "A_A") (pintype "passive"))
      (node (ref "E10") (pin "10") (pinfunction "O_10") (pintype "open_collector"))
      (node (ref "R8") (pin "1") (pinfunction "1_1") (pintype "passive"))
    )
    (net (code "44") (name "Net-(E11A-I1)") (class "Default")
      (node (ref "E11") (pin "10") (pinfunction "I1_10") (pintype "input"))
      (node (ref "E11") (pin "11") (pinfunction "I0_11") (pintype "input"))
      (node (ref "E11") (pin "5") (pinfunction "I1_5") (pintype "input"))
      (node (ref "E11") (pin "6") (pinfunction "I0_6") (pintype "input"))
      (node (ref "E12") (pin "5") (pinfunction "I1_5") (pintype "input"))
      (node (ref "E14") (pin "10") (pinfunction "O_10") (pintype "output"))
      (node (ref "R1") (pin "1") (pinfunction "1_1") (pintype "passive"))
    )
    (net (code "45") (name "Net-(E11A-O)") (class "Default")
      (node (ref "E11") (pin "3") (pinfunction "O_3") (pintype "output"))
      (node (ref "W1") (pin "1") (pinfunction "1_1") (pintype "passive"))
    )
    (net (code "46") (name "Net-(E11B-O)") (class "Default")
      (node (ref "E11") (pin "2") (pinfunction "O_2") (pintype "output"))
      (node (ref "E12") (pin "6") (pinfunction "I2_6") (pintype "input"))
    )
    (net (code "47") (name "Net-(E11C-O)") (class "Default")
      (node (ref "E11") (pin "14") (pinfunction "O_14") (pintype "output"))
      (node (ref "E12") (pin "9") (pinfunction "I3_9") (pintype "input"))
    )
    (net (code "48") (name "Net-(E11D-O)") (class "Default")
      (node (ref "E11") (pin "13") (pinfunction "O_13") (pintype "output"))
      (node (ref "E12") (pin "10") (pinfunction "I4_10") (pintype "input"))
    )
    (net (code "49") (name "Net-(E12A-I0)") (class "Default")
      (node (ref "E12") (pin "4") (pinfunction "I0_4") (pintype "input"))
      (node (ref "W1") (pin "2") (pinfunction "2_2") (pintype "passive"))
      (node (ref "W2") (pin "2") (pinfunction "2_2") (pintype "passive"))
    )
    (net (code "50") (name "Net-(E13D-O)") (class "Default")
      (node (ref "E13") (pin "13") (pinfunction "O_13") (pintype "output"))
      (node (ref "E14") (pin "11") (pinfunction "I_11") (pintype "input"))
    )
    (net (code "51") (name "Net-(E15A-P$5)") (class "Default")
      (node (ref "C40") (pin "2") (pinfunction "2_2") (pintype "passive"))
      (node (ref "E15") (pin "11") (pinfunction "P$5_11") (pintype "bidirectional"))
    )
    (net (code "52") (name "Net-(E15A-P$6)") (class "Default")
      (node (ref "C40") (pin "1") (pinfunction "1_1") (pintype "passive"))
      (node (ref "D1") (pin "C") (pinfunction "C_C") (pintype "passive"))
      (node (ref "E15") (pin "13") (pinfunction "P$6_13") (pintype "bidirectional"))
      (node (ref "R18") (pin "1") (pinfunction "1_1") (pintype "passive"))
    )
    (net (code "53") (name "Net-(E16C-I0)") (class "Default")
      (node (ref "E16") (pin "8") (pinfunction "I0_8") (pintype "input"))
      (node (ref "E16") (pin "9") (pinfunction "I1_9") (pintype "input"))
      (node (ref "E26") (pin "3") (pinfunction "O_3") (pintype "output"))
    )
    (net (code "54") (name "Net-(E17A-I0)") (class "Default")
      (node (ref "E17") (pin "2") (pinfunction "I0_2") (pintype "input"))
      (node (ref "E21") (pin "6") (pinfunction "O_6") (pintype "output"))
    )
    (net (code "55") (name "Net-(E17A-I1)") (class "Default")
      (node (ref "E17") (pin "11") (pinfunction "I0_11") (pintype "input"))
      (node (ref "E17") (pin "3") (pinfunction "I1_3") (pintype "input"))
      (node (ref "E17") (pin "5") (pinfunction "I0_5") (pintype "input"))
      (node (ref "E19") (pin "5") (pinfunction "Q_5") (pintype "output"))
    )
    (net (code "56") (name "Net-(E19A-CLK)") (class "Default")
      (node (ref "E19") (pin "3") (pinfunction "CLK_3") (pintype "input"))
      (node (ref "E23") (pin "8") (pinfunction "O_8") (pintype "output"))
    )
    (net (code "57") (name "Net-(E20C-I0)") (class "Default")
      (node (ref "E20") (pin "8") (pinfunction "I0_8") (pintype "input"))
      (node (ref "E21") (pin "10") (pinfunction "O_10") (pintype "output"))
      (node (ref "E22") (pin "9") (pinfunction "I0_9") (pintype "input"))
    )
    (net (code "58") (name "Net-(E20C-I1)") (class "Default")
      (node (ref "E20") (pin "9") (pinfunction "I1_9") (pintype "input"))
      (node (ref "E21") (pin "8") (pinfunction "O_8") (pintype "output"))
      (node (ref "E22") (pin "13") (pinfunction "I1_13") (pintype "input"))
    )
    (net (code "59") (name "Net-(E20D-O)") (class "Default")
      (node (ref "E20") (pin "13") (pinfunction "O_13") (pintype "output"))
      (node (ref "E24") (pin "10") (pinfunction "I1_10") (pintype "input"))
    )
    (net (code "60") (name "Net-(E21A-O)") (class "Default")
      (node (ref "E21") (pin "2") (pinfunction "O_2") (pintype "output"))
      (node (ref "E22") (pin "5") (pinfunction "I1_5") (pintype "input"))
    )
    (net (code "61") (name "Net-(E21B-O)") (class "Default")
      (node (ref "E21") (pin "4") (pinfunction "O_4") (pintype "output"))
      (node (ref "E22") (pin "2") (pinfunction "I1_2") (pintype "input"))
    )
    (net (code "62") (name "Net-(E24A-O)") (class "Default")
      (node (ref "E24") (pin "3") (pinfunction "O_3") (pintype "output"))
      (node (ref "E25") (pin "15") (pinfunction "A_15") (pintype "input"))
    )
    (net (code "63") (name "Net-(E24B-O)") (class "Default")
      (node (ref "E24") (pin "2") (pinfunction "O_2") (pintype "output"))
      (node (ref "E25") (pin "14") (pinfunction "B_14") (pintype "input"))
    )
    (net (code "64") (name "Net-(E24C-O)") (class "Default")
      (node (ref "E24") (pin "14") (pinfunction "O_14") (pintype "output"))
      (node (ref "E28") (pin "9") (pinfunction "I_9") (pintype "input"))
    )
    (net (code "65") (name "Net-(E24D-O)") (class "Default")
      (node (ref "E24") (pin "13") (pinfunction "O_13") (pintype "output"))
      (node (ref "E25") (pin "1") (pinfunction "C_1") (pintype "input"))
    )
    (net (code "66") (name "Net-(E26B-O)") (class "Default")
      (node (ref "E26") (pin "6") (pinfunction "O_6") (pintype "output"))
      (node (ref "E28") (pin "13") (pinfunction "I_13") (pintype "input"))
    )
    (net (code "67") (name "Net-(E26C-O)") (class "Default")
      (node (ref "E26") (pin "12") (pinfunction "I0_12") (pintype "input"))
      (node (ref "E26") (pin "8") (pinfunction "O_8") (pintype "output"))
    )
    (net (code "68") (name "Net-(E27D-O)") (class "Default")
      (node (ref "E27") (pin "11") (pinfunction "O_11") (pintype "output"))
      (node (ref "E28") (pin "3") (pinfunction "I_3") (pintype "input"))
      (node (ref "S1") (pin "1") (pinfunction "A1_1") (pintype "bidirectional"))
    )
    (net (code "69") (name "Net-(E28B-O)") (class "Default")
      (node (ref "E28") (pin "4") (pinfunction "O_4") (pintype "open_collector"))
      (node (ref "R13") (pin "1") (pinfunction "1_1") (pintype "passive"))
      (node (ref "S1") (pin "3") (pinfunction "A3_3") (pintype "bidirectional"))
    )
    (net (code "70") (name "Net-(Q1-B)") (class "Default")
      (node (ref "Q1") (pin "2") (pinfunction "B_2") (pintype "passive"))
      (node (ref "R14") (pin "2") (pinfunction "2_2") (pintype "passive"))
    )
    (net (code "71") (name "Net-(R10-Pad1)") (class "Default")
      (node (ref "R10") (pin "1") (pinfunction "1_1") (pintype "passive"))
      (node (ref "W4") (pin "2") (pinfunction "2_2") (pintype "passive"))
    )
    (net (code "72") (name "Net-(S2-A1)") (class "Default")
      (node (ref "C39") (pin "1") (pinfunction "1_1") (pintype "passive"))
      (node (ref "S2") (pin "1") (pinfunction "A1_1") (pintype "bidirectional"))
    )
    (net (code "73") (name "Net-(S2-A3)") (class "Default")
      (node (ref "C38") (pin "1") (pinfunction "1_1") (pintype "passive"))
      (node (ref "S2") (pin "3") (pinfunction "A3_3") (pintype "bidirectional"))
    )
    (net (code "74") (name "RED_DELAY") (class "Default")
      (node (ref "E2") (pin "5") (pinfunction "Q_5") (pintype "output"))
      (node (ref "E3") (pin "2") (pinfunction "I0_2") (pintype "input"))
      (node (ref "E3") (pin "9") (pinfunction "I1_9") (pintype "input"))
      (node (ref "TP1") (pin "TP") (pinfunction "TP_TP") (pintype "input"))
    )
    (net (code "75") (name "SET_DONE") (class "Default")
      (node (ref "E1") (pin "5") (pinfunction "Q_5") (pintype "output"))
      (node (ref "E3") (pin "6") (pinfunction "I1_6") (pintype "input"))
    )
    (net (code "76") (name "STORE") (class "Default")
      (node (ref "E5") (pin "9") (pinfunction "Q_9") (pintype "output"))
      (node (ref "E8") (pin "3") (pinfunction "I1_3") (pintype "input"))
    )
    (net (code "77") (name "TP3") (class "Default")
      (node (ref "E13") (pin "9") (pinfunction "I0_9") (pintype "input"))
      (node (ref "OMNIBUS") (pin "CH2") (pinfunction "1_CH2") (pintype "bidirectional"))
    )
    (net (code "78") (name "VCC") (class "Default")
      (node (ref "C1") (pin "1") (pinfunction "1_1") (pintype "passive"))
      (node (ref "C10") (pin "1") (pinfunction "1_1") (pintype "passive"))
      (node (ref "C11") (pin "1") (pinfunction "1_1") (pintype "passive"))
      (node (ref "C12") (pin "1") (pinfunction "1_1") (pintype "passive"))
      (node (ref "C13") (pin "1") (pinfunction "1_1") (pintype "passive"))
      (node (ref "C14") (pin "1") (pinfunction "1_1") (pintype "passive"))
      (node (ref "C15") (pin "1") (pinfunction "1_1") (pintype "passive"))
      (node (ref "C16") (pin "1") (pinfunction "1_1") (pintype "passive"))
      (node (ref "C17") (pin "1") (pinfunction "1_1") (pintype "passive"))
      (node (ref "C18") (pin "1") (pinfunction "1_1") (pintype "passive"))
      (node (ref "C19") (pin "1") (pinfunction "1_1") (pintype "passive"))
      (node (ref "C2") (pin "1") (pinfunction "1_1") (pintype "passive"))
      (node (ref "C20") (pin "1") (pinfunction "1_1") (pintype "passive"))
      (node (ref "C21") (pin "1") (pinfunction "1_1") (pintype "passive"))
      (node (ref "C22") (pin "1") (pinfunction "1_1") (pintype "passive"))
      (node (ref "C23") (pin "1") (pinfunction "1_1") (pintype "passive"))
      (node (ref "C24") (pin "1") (pinfunction "1_1") (pintype "passive"))
      (node (ref "C25") (pin "1") (pinfunction "1_1") (pintype "passive"))
      (node (ref "C26") (pin "1") (pinfunction "1_1") (pintype "passive"))
      (node (ref "C27") (pin "1") (pinfunction "1_1") (pintype "passive"))
      (node (ref "C28") (pin "1") (pinfunction "1_1") (pintype "passive"))
      (node (ref "C29") (pin "+") (pinfunction "+_+") (pintype "passive"))
      (node (ref "C3") (pin "1") (pinfunction "1_1") (pintype "passive"))
      (node (ref "C30") (pin "+") (pinfunction "+_+") (pintype "passive"))
      (node (ref "C31") (pin "+") (pinfunction "+_+") (pintype "passive"))
      (node (ref "C32") (pin "+") (pinfunction "+_+") (pintype "passive"))
      (node (ref "C4") (pin "1") (pinfunction "1_1") (pintype "passive"))
      (node (ref "C5") (pin "1") (pinfunction "1_1") (pintype "passive"))
      (node (ref "C6") (pin "1") (pinfunction "1_1") (pintype "passive"))
      (node (ref "C7") (pin "1") (pinfunction "1_1") (pintype "passive"))
      (node (ref "C8") (pin "1") (pinfunction "1_1") (pintype "passive"))
      (node (ref "C9") (pin "1") (pinfunction "1_1") (pintype "passive"))
      (node (ref "OMNIBUS") (pin "AA2") (pinfunction "1_AA2") (pintype "bidirectional"))
      (node (ref "OMNIBUS") (pin "BA2") (pinfunction "1_BA2") (pintype "bidirectional"))
      (node (ref "OMNIBUS") (pin "CA2") (pinfunction "1_CA2") (pintype "bidirectional"))
      (node (ref "R1") (pin "2") (pinfunction "2_2") (pintype "passive"))
      (node (ref "R10") (pin "2") (pinfunction "2_2") (pintype "passive"))
      (node (ref "R11") (pin "2") (pinfunction "2_2") (pintype "passive"))
      (node (ref "R12") (pin "2") (pinfunction "2_2") (pintype "passive"))
      (node (ref "R13") (pin "2") (pinfunction "2_2") (pintype "passive"))
      (node (ref "R15") (pin "2") (pinfunction "2_2") (pintype "passive"))
      (node (ref "R16") (pin "2") (pinfunction "2_2") (pintype "passive"))
      (node (ref "R17") (pin "2") (pinfunction "2_2") (pintype "passive"))
      (node (ref "R18") (pin "2") (pinfunction "2_2") (pintype "passive"))
      (node (ref "R19") (pin "2") (pinfunction "2_2") (pintype "passive"))
      (node (ref "R2") (pin "2") (pinfunction "2_2") (pintype "passive"))
      (node (ref "R20") (pin "2") (pinfunction "2_2") (pintype "passive"))
      (node (ref "R21") (pin "2") (pinfunction "2_2") (pintype "passive"))
      (node (ref "R22") (pin "2") (pinfunction "2_2") (pintype "passive"))
      (node (ref "R3") (pin "2") (pinfunction "2_2") (pintype "passive"))
      (node (ref "R4") (pin "2") (pinfunction "2_2") (pintype "passive"))
      (node (ref "R5") (pin "2") (pinfunction "2_2") (pintype "passive"))
      (node (ref "R6") (pin "2") (pinfunction "2_2") (pintype "passive"))
      (node (ref "R7") (pin "2") (pinfunction "2_2") (pintype "passive"))
      (node (ref "R8") (pin "2") (pinfunction "2_2") (pintype "passive"))
      (node (ref "R9") (pin "2") (pinfunction "2_2") (pintype "passive"))
    )
    (net (code "79") (name "WRITE_THRU") (class "Default")
      (node (ref "E10") (pin "9") (pinfunction "I_9") (pintype "input"))
      (node (ref "E5") (pin "5") (pinfunction "Q_5") (pintype "output"))
      (node (ref "E8") (pin "12") (pinfunction "I1_12") (pintype "input"))
    )
    (net (code "80") (name "Z_PULSE") (class "Default")
      (node (ref "E27") (pin "12") (pinfunction "I0_12") (pintype "input"))
      (node (ref "F") (pin "A2") (pinfunction "P_A2") (pintype "passive"))
      (node (ref "R11") (pin "1") (pinfunction "1_1") (pintype "passive"))
    )
    (net (code "81") (name "unconnected-(E1A-~{Q}-Pad4)") (class "Default")
      (node (ref "E1") (pin "4") (pinfunction "~{Q}_4") (pintype "output"))
    )
    (net (code "82") (name "unconnected-(E2A-~{Q}-Pad4)") (class "Default")
      (node (ref "E2") (pin "4") (pinfunction "~{Q}_4") (pintype "output"))
    )
    (net (code "83") (name "unconnected-(E2B-~{Q}-Pad12)") (class "Default")
      (node (ref "E2") (pin "12") (pinfunction "~{Q}_12") (pintype "output"))
    )
    (net (code "84") (name "unconnected-(E4A-Q-Pad8)") (class "Default")
      (node (ref "E4") (pin "8") (pinfunction "Q_8") (pintype "output"))
    )
    (net (code "85") (name "unconnected-(E5A-~{Q}-Pad6)") (class "Default")
      (node (ref "E5") (pin "6") (pinfunction "~{Q}_6") (pintype "output"))
    )
    (net (code "86") (name "unconnected-(E6A-~{Q}-Pad6)") (class "Default")
      (node (ref "E6") (pin "6") (pinfunction "~{Q}_6") (pintype "output"))
    )
    (net (code "87") (name "unconnected-(E15A-Q-Pad8)") (class "Default")
      (node (ref "E15") (pin "8") (pinfunction "Q_8") (pintype "output"))
    )
    (net (code "88") (name "unconnected-(E18A-~{Q}-Pad6)") (class "Default")
      (node (ref "E18") (pin "6") (pinfunction "~{Q}_6") (pintype "output"))
    )
    (net (code "89") (name "unconnected-(E18B-~{Q}-Pad8)") (class "Default")
      (node (ref "E18") (pin "8") (pinfunction "~{Q}_8") (pintype "output"))
    )
    (net (code "90") (name "unconnected-(E19A-~{Q}-Pad6)") (class "Default")
      (node (ref "E19") (pin "6") (pinfunction "~{Q}_6") (pintype "output"))
    )
    (net (code "91") (name "unconnected-(E25A-8-Pad6)") (class "Default")
      (node (ref "E25") (pin "6") (pinfunction "8_6") (pintype "output"))
    )
    (net (code "92") (name "unconnected-(E25A-9-Pad7)") (class "Default")
      (node (ref "E25") (pin "7") (pinfunction "9_7") (pintype "output"))
    )
    (net (code "93") (name "~{BTP3}") (class "Default")
      (node (ref "E13") (pin "14") (pinfunction "O_14") (pintype "output"))
      (node (ref "E14") (pin "9") (pinfunction "I_9") (pintype "input"))
      (node (ref "E20") (pin "12") (pinfunction "I1_12") (pintype "input"))
      (node (ref "E20") (pin "3") (pinfunction "I1_3") (pintype "input"))
    )
    (net (code "94") (name "~{B_DICD}") (class "Default")
      (node (ref "E22") (pin "3") (pinfunction "O_3") (pintype "output"))
      (node (ref "E23") (pin "5") (pinfunction "I3_5") (pintype "input"))
    )
    (net (code "95") (name "~{B_DIXY}") (class "Default")
      (node (ref "E15") (pin "1") (pinfunction "P$1_1") (pintype "input"))
      (node (ref "E15") (pin "2") (pinfunction "P$2_2") (pintype "input"))
      (node (ref "E22") (pin "6") (pinfunction "O_6") (pintype "output"))
      (node (ref "E23") (pin "4") (pinfunction "I2_4") (pintype "input"))
    )
    (net (code "96") (name "~{B_LOAD_EN}") (class "Default")
      (node (ref "E23") (pin "2") (pinfunction "I1_2") (pintype "input"))
      (node (ref "E26") (pin "11") (pinfunction "O_11") (pintype "output"))
    )
    (net (code "97") (name "~{C0}") (class "Default")
      (node (ref "E16") (pin "10") (pinfunction "O_10") (pintype "open_collector"))
      (node (ref "OMNIBUS") (pin "CE1") (pinfunction "1_CE1") (pintype "bidirectional"))
    )
    (net (code "98") (name "~{C1}") (class "Default")
      (node (ref "E16") (pin "13") (pinfunction "O_13") (pintype "open_collector"))
      (node (ref "OMNIBUS") (pin "CH1") (pinfunction "1_CH1") (pintype "bidirectional"))
    )
    (net (code "99") (name "~{CHAN}") (class "Default")
      (node (ref "E28") (pin "2") (pinfunction "O_2") (pintype "open_collector"))
      (node (ref "F") (pin "R1") (pinfunction "P_R1") (pintype "passive"))
      (node (ref "R12") (pin "1") (pinfunction "1_1") (pintype "passive"))
    )
    (net (code "100") (name "~{CLEAR_DONE}") (class "Default")
      (node (ref "E26") (pin "10") (pinfunction "I1_10") (pintype "input"))
      (node (ref "E3") (pin "13") (pinfunction "O_13") (pintype "output"))
    )
    (net (code "101") (name "~{CLEAR}") (class "Default")
      (node (ref "E18") (pin "1") (pinfunction "CLR_1") (pintype "input"))
      (node (ref "E18") (pin "13") (pinfunction "CLR_13") (pintype "input"))
      (node (ref "E23") (pin "1") (pinfunction "I0_1") (pintype "input"))
      (node (ref "E28") (pin "6") (pinfunction "O_6") (pintype "open_collector"))
      (node (ref "E5") (pin "1") (pinfunction "CLR_1") (pintype "input"))
      (node (ref "E5") (pin "13") (pinfunction "CLR_13") (pintype "input"))
      (node (ref "E6") (pin "13") (pinfunction "CLR_13") (pintype "input"))
      (node (ref "R5") (pin "1") (pinfunction "1_1") (pintype "passive"))
    )
    (net (code "102") (name "~{CL_DONE}") (class "Default")
      (node (ref "E19") (pin "1") (pinfunction "CLR_1") (pintype "input"))
      (node (ref "E23") (pin "6") (pinfunction "O_6") (pintype "output"))
    )
    (net (code "103") (name "~{COLOR}") (class "Default")
      (node (ref "E10") (pin "11") (pinfunction "I_11") (pintype "input"))
      (node (ref "E2") (pin "2") (pinfunction "B_2") (pintype "input"))
      (node (ref "E6") (pin "8") (pinfunction "~{Q}_8") (pintype "output"))
      (node (ref "E7") (pin "6") (pinfunction "I1_6") (pintype "input"))
    )
    (net (code "104") (name "~{COL_RED}") (class "Default")
      (node (ref "E7") (pin "1") (pinfunction "O_1") (pintype "open_collector"))
      (node (ref "F") (pin "L1") (pinfunction "P_L1") (pintype "passive"))
      (node (ref "R21") (pin "1") (pinfunction "1_1") (pintype "passive"))
    )
    (net (code "105") (name "~{DATA00}") (class "Default")
      (node (ref "E17") (pin "13") (pinfunction "O_13") (pintype "open_collector"))
      (node (ref "OMNIBUS") (pin "AR1") (pinfunction "1_AR1") (pintype "bidirectional"))
    )
    (net (code "106") (name "~{DATA06}") (class "Default")
      (node (ref "E8") (pin "13") (pinfunction "O_13") (pintype "open_collector"))
      (node (ref "E9") (pin "9") (pinfunction "I0_9") (pintype "input"))
      (node (ref "OMNIBUS") (pin "BU1") (pinfunction "1_BU1") (pintype "bidirectional"))
    )
    (net (code "107") (name "~{DATA07}") (class "Default")
      (node (ref "E8") (pin "1") (pinfunction "O_1") (pintype "open_collector"))
      (node (ref "E9") (pin "7") (pinfunction "I1_7") (pintype "input"))
      (node (ref "OMNIBUS") (pin "BV1") (pinfunction "1_BV1") (pintype "bidirectional"))
    )
    (net (code "108") (name "~{DATA08}") (class "Default")
      (node (ref "E9") (pin "4") (pinfunction "I0_4") (pintype "input"))
      (node (ref "OMNIBUS") (pin "DR1") (pinfunction "1_DR1") (pintype "bidirectional"))
    )
    (net (code "109") (name "~{DATA09}") (class "Default")
      (node (ref "E8") (pin "10") (pinfunction "O_10") (pintype "open_collector"))
      (node (ref "E9") (pin "12") (pinfunction "I1_12") (pintype "input"))
      (node (ref "OMNIBUS") (pin "DS1") (pinfunction "1_DS1") (pintype "bidirectional"))
    )
    (net (code "110") (name "~{DATA10}") (class "Default")
      (node (ref "E13") (pin "4") (pinfunction "I0_4") (pintype "input"))
      (node (ref "E16") (pin "1") (pinfunction "O_1") (pintype "open_collector"))
      (node (ref "OMNIBUS") (pin "DU1") (pinfunction "1_DU1") (pintype "bidirectional"))
    )
    (net (code "111") (name "~{DATA11}") (class "Default")
      (node (ref "E13") (pin "6") (pinfunction "I0_6") (pintype "input"))
      (node (ref "E16") (pin "4") (pinfunction "O_4") (pintype "open_collector"))
      (node (ref "OMNIBUS") (pin "DV1") (pinfunction "1_DV1") (pintype "bidirectional"))
    )
    (net (code "112") (name "~{DEL_1}") (class "Default")
      (node (ref "E15") (pin "6") (pinfunction "~{Q}_6") (pintype "output"))
      (node (ref "E23") (pin "9") (pinfunction "I0_9") (pintype "input"))
      (node (ref "E27") (pin "13") (pinfunction "I1_13") (pintype "input"))
    )
    (net (code "113") (name "~{DICD}") (class "Default")
      (node (ref "E21") (pin "3") (pinfunction "I_3") (pintype "input"))
      (node (ref "E25") (pin "12") (pinfunction "1_12") (pintype "output"))
    )
    (net (code "114") (name "~{DICL}") (class "Default")
      (node (ref "E20") (pin "11") (pinfunction "I0_11") (pintype "input"))
      (node (ref "E25") (pin "13") (pinfunction "0_13") (pintype "output"))
    )
    (net (code "115") (name "~{DILE}") (class "Default")
      (node (ref "E20") (pin "2") (pinfunction "I0_2") (pintype "input"))
      (node (ref "E25") (pin "4") (pinfunction "6_4") (pintype "output"))
      (node (ref "E26") (pin "1") (pinfunction "I0_1") (pintype "input"))
      (node (ref "E26") (pin "4") (pinfunction "I0_4") (pintype "input"))
      (node (ref "F") (pin "P1") (pinfunction "P_P1") (pintype "passive"))
    )
    (net (code "116") (name "~{DILX}") (class "Default")
      (node (ref "E21") (pin "11") (pinfunction "I_11") (pintype "input"))
      (node (ref "E25") (pin "10") (pinfunction "3_10") (pintype "output"))
    )
    (net (code "117") (name "~{DILY}") (class "Default")
      (node (ref "E21") (pin "9") (pinfunction "I_9") (pintype "input"))
      (node (ref "E25") (pin "9") (pinfunction "4_9") (pintype "output"))
    )
    (net (code "118") (name "~{DIRE}") (class "Default")
      (node (ref "E21") (pin "13") (pinfunction "I_13") (pintype "input"))
      (node (ref "E25") (pin "5") (pinfunction "7_5") (pintype "output"))
      (node (ref "E26") (pin "2") (pinfunction "I1_2") (pintype "input"))
      (node (ref "F") (pin "B2") (pinfunction "P_B2") (pintype "passive"))
    )
    (net (code "119") (name "~{DISD}") (class "Default")
      (node (ref "E21") (pin "5") (pinfunction "I_5") (pintype "input"))
      (node (ref "E25") (pin "11") (pinfunction "2_11") (pintype "output"))
    )
    (net (code "120") (name "~{DIXY}") (class "Default")
      (node (ref "E21") (pin "1") (pinfunction "I_1") (pintype "input"))
      (node (ref "E25") (pin "3") (pinfunction "5_3") (pintype "output"))
    )
    (net (code "121") (name "~{DLY_DONE}") (class "Default")
      (node (ref "E23") (pin "12") (pinfunction "I2_12") (pintype "input"))
      (node (ref "E3") (pin "1") (pinfunction "O_1") (pintype "output"))
    )
    (net (code "122") (name "~{ERASE_INTERVAL}") (class "Default")
      (node (ref "F") (pin "D2") (pinfunction "P_D2") (pintype "passive"))
      (node (ref "R14") (pin "1") (pinfunction "1_1") (pintype "passive"))
    )
    (net (code "123") (name "~{ERASE}") (class "Default")
      (node (ref "E10") (pin "4") (pinfunction "O_4") (pintype "open_collector"))
      (node (ref "F") (pin "K1") (pinfunction "P_K1") (pintype "passive"))
    )
    (net (code "124") (name "~{INTERNAL_IO}") (class "Default")
      (node (ref "E17") (pin "10") (pinfunction "O_10") (pintype "open_collector"))
      (node (ref "OMNIBUS") (pin "CL1") (pinfunction "1_CL1") (pintype "bidirectional"))
    )
    (net (code "125") (name "~{INTERRUPT}") (class "Default")
      (node (ref "E17") (pin "4") (pinfunction "O_4") (pintype "open_collector"))
      (node (ref "OMNIBUS") (pin "CP1") (pinfunction "1_CP1") (pintype "bidirectional"))
    )
    (net (code "126") (name "~{IOT}") (class "Default")
      (node (ref "E24") (pin "12") (pinfunction "I1_12") (pintype "input"))
      (node (ref "E24") (pin "5") (pinfunction "I1_5") (pintype "input"))
      (node (ref "E24") (pin "6") (pinfunction "I0_6") (pintype "input"))
      (node (ref "E25") (pin "2") (pinfunction "D_2") (pintype "input"))
      (node (ref "E28") (pin "10") (pinfunction "O_10") (pintype "open_collector"))
      (node (ref "R2") (pin "1") (pinfunction "1_1") (pintype "passive"))
    )
    (net (code "127") (name "~{LD_DEL}") (class "Default")
      (node (ref "E23") (pin "13") (pinfunction "I3_13") (pintype "input"))
      (node (ref "E4") (pin "6") (pinfunction "~{Q}_6") (pintype "output"))
    )
    (net (code "128") (name "~{LOAD_DATA}") (class "Default")
      (node (ref "E13") (pin "5") (pinfunction "I1_5") (pintype "input"))
      (node (ref "E13") (pin "7") (pinfunction "I1_7") (pintype "input"))
      (node (ref "E28") (pin "12") (pinfunction "O_12") (pintype "open_collector"))
      (node (ref "E9") (pin "10") (pinfunction "I1_10") (pintype "input"))
      (node (ref "E9") (pin "11") (pinfunction "I0_11") (pintype "input"))
      (node (ref "E9") (pin "5") (pinfunction "I1_5") (pintype "input"))
      (node (ref "E9") (pin "6") (pinfunction "I0_6") (pintype "input"))
      (node (ref "R6") (pin "1") (pinfunction "1_1") (pintype "passive"))
    )
    (net (code "129") (name "~{LOAD_EN}") (class "Default")
      (node (ref "E20") (pin "10") (pinfunction "O_10") (pintype "output"))
      (node (ref "E26") (pin "5") (pinfunction "I1_5") (pintype "input"))
      (node (ref "E26") (pin "9") (pinfunction "I0_9") (pintype "input"))
      (node (ref "E4") (pin "1") (pinfunction "P$1_1") (pintype "input"))
      (node (ref "E4") (pin "2") (pinfunction "P$2_2") (pintype "input"))
      (node (ref "F") (pin "V1") (pinfunction "P_V1") (pintype "passive"))
    )
    (net (code "130") (name "~{MD3}") (class "Default")
      (node (ref "E11") (pin "12") (pinfunction "I1_12") (pintype "input"))
      (node (ref "OMNIBUS") (pin "AP1") (pinfunction "1_AP1") (pintype "bidirectional"))
    )
    (net (code "131") (name "~{MD4}") (class "Default")
      (node (ref "E11") (pin "9") (pinfunction "I0_9") (pintype "input"))
      (node (ref "OMNIBUS") (pin "BK1") (pinfunction "1_BK1") (pintype "bidirectional"))
    )
    (net (code "132") (name "~{MD5}") (class "Default")
      (node (ref "E11") (pin "4") (pinfunction "I0_4") (pintype "input"))
      (node (ref "OMNIBUS") (pin "BL1") (pinfunction "1_BL1") (pintype "bidirectional"))
      (node (ref "W2") (pin "1") (pinfunction "1_1") (pintype "passive"))
    )
    (net (code "133") (name "~{MD6}") (class "Default")
      (node (ref "E12") (pin "11") (pinfunction "I5_11") (pintype "input"))
      (node (ref "OMNIBUS") (pin "BM1") (pinfunction "1_BM1") (pintype "bidirectional"))
    )
    (net (code "134") (name "~{MD7}") (class "Default")
      (node (ref "E11") (pin "7") (pinfunction "I1_7") (pintype "input"))
      (node (ref "OMNIBUS") (pin "BP1") (pinfunction "1_BP1") (pintype "bidirectional"))
    )
    (net (code "135") (name "~{MD8}") (class "Default")
      (node (ref "E12") (pin "12") (pinfunction "I6_12") (pintype "input"))
      (node (ref "OMNIBUS") (pin "DK1") (pinfunction "1_DK1") (pintype "bidirectional"))
    )
    (net (code "136") (name "~{MD9}") (class "Default")
      (node (ref "E24") (pin "11") (pinfunction "I0_11") (pintype "input"))
      (node (ref "OMNIBUS") (pin "DL1") (pinfunction "1_DL1") (pintype "bidirectional"))
    )
    (net (code "137") (name "~{MD10}") (class "Default")
      (node (ref "E24") (pin "7") (pinfunction "I1_7") (pintype "input"))
      (node (ref "OMNIBUS") (pin "DM1") (pinfunction "1_DM1") (pintype "bidirectional"))
    )
    (net (code "138") (name "~{MD11}") (class "Default")
      (node (ref "E24") (pin "4") (pinfunction "I0_4") (pintype "input"))
      (node (ref "OMNIBUS") (pin "DP1") (pinfunction "1_DP1") (pintype "bidirectional"))
    )
    (net (code "139") (name "~{NON_STORE}") (class "Default")
      (node (ref "E10") (pin "12") (pinfunction "O_12") (pintype "open_collector"))
      (node (ref "F") (pin "C2") (pinfunction "P_C2") (pintype "passive"))
    )
    (net (code "140") (name "~{PAUSE}") (class "Default")
      (node (ref "E13") (pin "12") (pinfunction "I1_12") (pintype "input"))
      (node (ref "OMNIBUS") (pin "CD1") (pinfunction "1_CD1") (pintype "bidirectional"))
    )
    (net (code "141") (name "~{SET_DONE}") (class "Default")
      (node (ref "E1") (pin "12") (pinfunction "~{Q}_12") (pintype "output"))
      (node (ref "E23") (pin "10") (pinfunction "I1_10") (pintype "input"))
    )
    (net (code "142") (name "~{SKIP}") (class "Default")
      (node (ref "E17") (pin "1") (pinfunction "O_1") (pintype "open_collector"))
      (node (ref "OMNIBUS") (pin "CS1") (pinfunction "1_CS1") (pintype "bidirectional"))
    )
    (net (code "143") (name "~{STORE}") (class "Default")
      (node (ref "E10") (pin "13") (pinfunction "I_13") (pintype "input"))
      (node (ref "E5") (pin "8") (pinfunction "~{Q}_8") (pintype "output"))
      (node (ref "E7") (pin "5") (pinfunction "I0_5") (pintype "input"))
    )
    (net (code "144") (name "~{WRITE_THRU}") (class "Default")
      (node (ref "E10") (pin "8") (pinfunction "O_8") (pintype "open_collector"))
      (node (ref "F") (pin "M1") (pinfunction "P_M1") (pintype "passive"))
    )
  )
)
